# HighCurrentFetVcc.net
KiCad netlist of a schematic drawn in Altium Designer
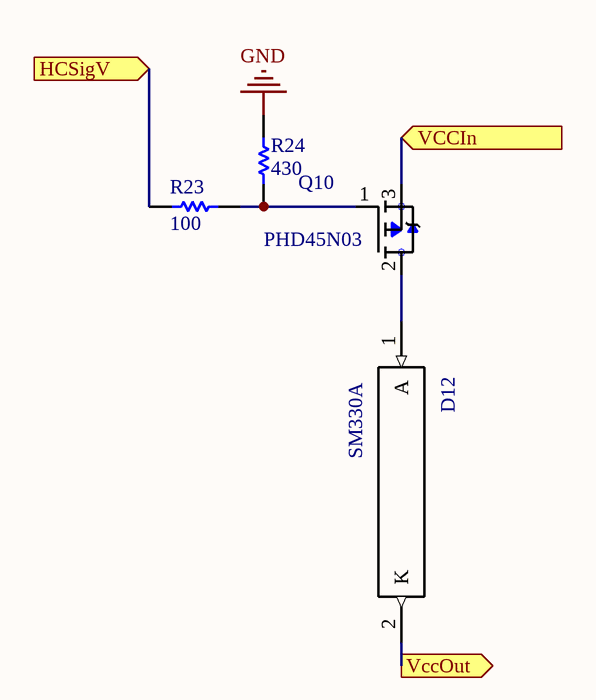
[diagram p0: HighCurrentFetVcc.SchDoc]

(export (version "E")
  (design (tool "Eeschema 10.0.6"))
  (components
    (comp (ref "D12")
      (value "SM330A")
      (footprint "*DIOM5227X270N_S1M(Primary)")
      (description "SCHOTTKY RECTIFIER 2A; Voltage Vrrm: 60V; Diode Case Style: DO-214AC; Case Style: DO-214AC")
      (fields (field (name "MF") "STMicroelectronics") (field (name "MP") "STPS2L60A"))
      (libsource (lib "STPS2L60A") (part "STPS2L60A"))
    )
    (comp (ref "Q10")
      (value "PHD45N03")
      (footprint "*DPAK228P998X235-3N")
      (description "P-Channel 40 V 10.6 mOhm OptiMOSآ®-P2 Power-Transistor -PG-TO-252-3")
      (fields (field (name "MP") "IPD50P04P4L-11") (field (name "MF") "Infineon Technologies"))
      (libsource (lib "IPD50P04P4L-11") (part "IPD50P04P4L-11"))
    )
    (comp (ref "R23")
      (value "100")
      (footprint "6-0805_L")
      (description "Resistor")
      (fields (field (name "Comment") "R100") (field (name "PUBLISHER") "Altium Limited"))
      (libsource (lib "Miscellaneous Devices") (part "Res1"))
    )
    (comp (ref "R24")
      (value "430")
      (footprint "6-0805_L")
      (description "Resistor")
      (fields (field (name "Comment") "R430") (field (name "PUBLISHER") "Altium Limited"))
      (libsource (lib "Miscellaneous Devices") (part "Res1"))
    )
  )
  (nets
    (net (code "1") (name "/HCSigV") (class "Default")
      (node (ref "R23") (pin "1") (pinfunction "1_1") (pintype "passive"))
    )
    (net (code "2") (name "/VCCIn") (class "Default")
      (node (ref "Q10") (pin "3") (pinfunction "S_3") (pintype "passive"))
    )
    (net (code "3") (name "/VccOut") (class "Default")
      (node (ref "D12") (pin "2") (pinfunction "K_2") (pintype "output"))
    )
    (net (code "4") (name "GND") (class "Default")
      (node (ref "R24") (pin "1") (pinfunction "1_1") (pintype "passive"))
    )
    (net (code "5") (name "Net-(D12-A)") (class "Default")
      (node (ref "D12") (pin "1") (pinfunction "A_1") (pintype "input"))
      (node (ref "Q10") (pin "2") (pinfunction "D_2") (pintype "passive"))
    )
    (net (code "6") (name "Net-(Q10-G)") (class "Default")
      (node (ref "Q10") (pin "1") (pinfunction "G_1") (pintype "passive"))
      (node (ref "R23") (pin "2") (pinfunction "2_2") (pintype "passive"))
      (node (ref "R24") (pin "2") (pinfunction "2_2") (pintype "passive"))
    )
  )
)
